# Led.net
KiCad netlist of a schematic drawn in Altium Designer
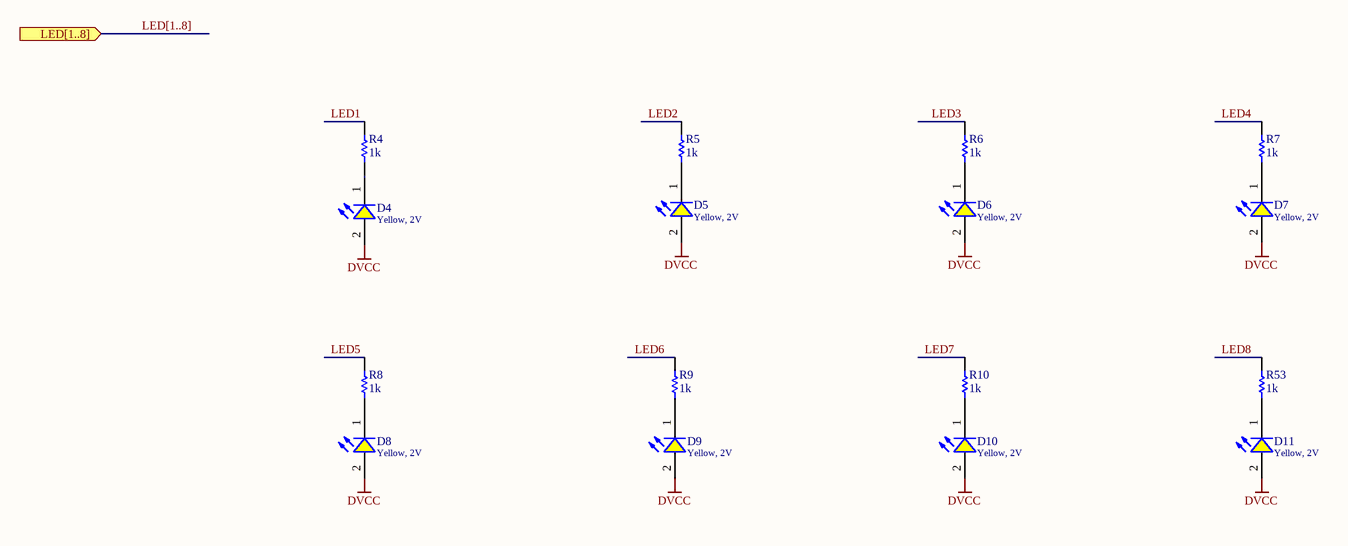
[diagram p0: Led.SchDoc]

(export (version "E")
  (design (tool "Eeschema 10.0.6"))
  (components
    (comp (ref "D4")
      (value "Yellow, 2V")
      (footprint "WL-SMCW_0603_H=0.7mm")
      (description "WL-SMCW SMT Mono-color Chip LED Waterclear, size 0603, Yellow, 2V, 140deg")
      (fields (field (name "MPN") "150060YS75000") (field (name "MF") "Wurth Elektronik"))
      (libsource (lib "Componentes_SOC") (part "150060YS75000"))
    )
    (comp (ref "D5")
      (value "Yellow, 2V")
      (footprint "WL-SMCW_0603_H=0.7mm")
      (description "WL-SMCW SMT Mono-color Chip LED Waterclear, size 0603, Yellow, 2V, 140deg")
      (fields (field (name "MPN") "150060YS75000") (field (name "MF") "Wurth Elektronik"))
      (libsource (lib "Componentes_SOC") (part "150060YS75000"))
    )
    (comp (ref "D6")
      (value "Yellow, 2V")
      (footprint "WL-SMCW_0603_H=0.7mm")
      (description "WL-SMCW SMT Mono-color Chip LED Waterclear, size 0603, Yellow, 2V, 140deg")
      (fields (field (name "MPN") "150060YS75000") (field (name "MF") "Wurth Elektronik"))
      (libsource (lib "Componentes_SOC") (part "150060YS75000"))
    )
    (comp (ref "D7")
      (value "Yellow, 2V")
      (footprint "WL-SMCW_0603_H=0.7mm")
      (description "WL-SMCW SMT Mono-color Chip LED Waterclear, size 0603, Yellow, 2V, 140deg")
      (fields (field (name "MPN") "150060YS75000") (field (name "MF") "Wurth Elektronik"))
      (libsource (lib "Componentes_SOC") (part "150060YS75000"))
    )
    (comp (ref "D8")
      (value "Yellow, 2V")
      (footprint "WL-SMCW_0603_H=0.7mm")
      (description "WL-SMCW SMT Mono-color Chip LED Waterclear, size 0603, Yellow, 2V, 140deg")
      (fields (field (name "MPN") "150060YS75000") (field (name "MF") "Wurth Elektronik"))
      (libsource (lib "Componentes_SOC") (part "150060YS75000"))
    )
    (comp (ref "D9")
      (value "Yellow, 2V")
      (footprint "WL-SMCW_0603_H=0.7mm")
      (description "WL-SMCW SMT Mono-color Chip LED Waterclear, size 0603, Yellow, 2V, 140deg")
      (fields (field (name "MPN") "150060YS75000") (field (name "MF") "Wurth Elektronik"))
      (libsource (lib "Componentes_SOC") (part "150060YS75000"))
    )
    (comp (ref "D10")
      (value "Yellow, 2V")
      (footprint "WL-SMCW_0603_H=0.7mm")
      (description "WL-SMCW SMT Mono-color Chip LED Waterclear, size 0603, Yellow, 2V, 140deg")
      (fields (field (name "MPN") "150060YS75000") (field (name "MF") "Wurth Elektronik"))
      (libsource (lib "Componentes_SOC") (part "150060YS75000"))
    )
    (comp (ref "D11")
      (value "Yellow, 2V")
      (footprint "WL-SMCW_0603_H=0.7mm")
      (description "WL-SMCW SMT Mono-color Chip LED Waterclear, size 0603, Yellow, 2V, 140deg")
      (fields (field (name "MPN") "150060YS75000") (field (name "MF") "Wurth Elektronik"))
      (libsource (lib "Componentes_SOC") (part "150060YS75000"))
    )
    (comp (ref "R4")
      (value "1k")
      (footprint "RES_0603")
      (fields
        (field (name "MPN") "RC0603FR-071KL")
        (field (name "TOLERANCE") "1%")
        (field (name "PUBLISHER") "Altium Limited")
      )
      (libsource (lib "Componentes_SOC") (part "Res0603"))
    )
    (comp (ref "R5")
      (value "1k")
      (footprint "RES_0603")
      (fields
        (field (name "MPN") "RC0603FR-071KL")
        (field (name "TOLERANCE") "1%")
        (field (name "PUBLISHER") "Altium Limited")
      )
      (libsource (lib "Componentes_SOC") (part "Res0603"))
    )
    (comp (ref "R6")
      (value "1k")
      (footprint "RES_0603")
      (fields
        (field (name "MPN") "RC0603FR-071KL")
        (field (name "TOLERANCE") "1%")
        (field (name "PUBLISHER") "Altium Limited")
      )
      (libsource (lib "Componentes_SOC") (part "Res0603"))
    )
    (comp (ref "R7")
      (value "1k")
      (footprint "RES_0603")
      (fields
        (field (name "MPN") "RC0603FR-071KL")
        (field (name "TOLERANCE") "1%")
        (field (name "PUBLISHER") "Altium Limited")
      )
      (libsource (lib "Componentes_SOC") (part "Res0603"))
    )
    (comp (ref "R8")
      (value "1k")
      (footprint "RES_0603")
      (fields
        (field (name "MPN") "RC0603FR-071KL")
        (field (name "TOLERANCE") "1%")
        (field (name "PUBLISHER") "Altium Limited")
      )
      (libsource (lib "Componentes_SOC") (part "Res0603"))
    )
    (comp (ref "R9")
      (value "1k")
      (footprint "RES_0603")
      (fields
        (field (name "MPN") "RC0603FR-071KL")
        (field (name "TOLERANCE") "1%")
        (field (name "PUBLISHER") "Altium Limited")
      )
      (libsource (lib "Componentes_SOC") (part "Res0603"))
    )
    (comp (ref "R10")
      (value "1k")
      (footprint "RES_0603")
      (fields
        (field (name "MPN") "RC0603FR-071KL")
        (field (name "TOLERANCE") "1%")
        (field (name "PUBLISHER") "Altium Limited")
      )
      (libsource (lib "Componentes_SOC") (part "Res0603"))
    )
    (comp (ref "R53")
      (value "1k")
      (footprint "RES_0603")
      (fields
        (field (name "MPN") "RC0603FR-071KL")
        (field (name "TOLERANCE") "1%")
        (field (name "PUBLISHER") "Altium Limited")
      )
      (libsource (lib "Componentes_SOC") (part "Res0603"))
    )
  )
  (nets
    (net (code "1") (name "/LED1") (class "Default")
      (node (ref "R4") (pin "2") (pinfunction "2_2") (pintype "passive"))
    )
    (net (code "2") (name "/LED2") (class "Default")
      (node (ref "R5") (pin "2") (pinfunction "2_2") (pintype "passive"))
    )
    (net (code "3") (name "/LED3") (class "Default")
      (node (ref "R6") (pin "2") (pinfunction "2_2") (pintype "passive"))
    )
    (net (code "4") (name "/LED4") (class "Default")
      (node (ref "R7") (pin "2") (pinfunction "2_2") (pintype "passive"))
    )
    (net (code "5") (name "/LED5") (class "Default")
      (node (ref "R8") (pin "2") (pinfunction "2_2") (pintype "passive"))
    )
    (net (code "6") (name "/LED6") (class "Default")
      (node (ref "R9") (pin "2") (pinfunction "2_2") (pintype "passive"))
    )
    (net (code "7") (name "/LED7") (class "Default")
      (node (ref "R10") (pin "2") (pinfunction "2_2") (pintype "passive"))
    )
    (net (code "8") (name "/LED8") (class "Default")
      (node (ref "R53") (pin "2") (pinfunction "2_2") (pintype "passive"))
    )
    (net (code "10") (name "DVCC") (class "Default")
      (node (ref "D10") (pin "2") (pinfunction "A_2") (pintype "passive"))
      (node (ref "D11") (pin "2") (pinfunction "A_2") (pintype "passive"))
      (node (ref "D4") (pin "2") (pinfunction "A_2") (pintype "passive"))
      (node (ref "D5") (pin "2") (pinfunction "A_2") (pintype "passive"))
      (node (ref "D6") (pin "2") (pinfunction "A_2") (pintype "passive"))
      (node (ref "D7") (pin "2") (pinfunction "A_2") (pintype "passive"))
      (node (ref "D8") (pin "2") (pinfunction "A_2") (pintype "passive"))
      (node (ref "D9") (pin "2") (pinfunction "A_2") (pintype "passive"))
    )
    (net (code "11") (name "Net-(D4-K)") (class "Default")
      (node (ref "D4") (pin "1") (pinfunction "K_1") (pintype "passive"))
      (node (ref "R4") (pin "1") (pinfunction "1_1") (pintype "passive"))
    )
    (net (code "12") (name "Net-(D5-K)") (class "Default")
      (node (ref "D5") (pin "1") (pinfunction "K_1") (pintype "passive"))
      (node (ref "R5") (pin "1") (pinfunction "1_1") (pintype "passive"))
    )
    (net (code "13") (name "Net-(D6-K)") (class "Default")
      (node (ref "D6") (pin "1") (pinfunction "K_1") (pintype "passive"))
      (node (ref "R6") (pin "1") (pinfunction "1_1") (pintype "passive"))
    )
    (net (code "14") (name "Net-(D7-K)") (class "Default")
      (node (ref "D7") (pin "1") (pinfunction "K_1") (pintype "passive"))
      (node (ref "R7") (pin "1") (pinfunction "1_1") (pintype "passive"))
    )
    (net (code "15") (name "Net-(D8-K)") (class "Default")
      (node (ref "D8") (pin "1") (pinfunction "K_1") (pintype "passive"))
      (node (ref "R8") (pin "1") (pinfunction "1_1") (pintype "passive"))
    )
    (net (code "16") (name "Net-(D9-K)") (class "Default")
      (node (ref "D9") (pin "1") (pinfunction "K_1") (pintype "passive"))
      (node (ref "R9") (pin "1") (pinfunction "1_1") (pintype "passive"))
    )
    (net (code "17") (name "Net-(D10-K)") (class "Default")
      (node (ref "D10") (pin "1") (pinfunction "K_1") (pintype "passive"))
      (node (ref "R10") (pin "1") (pinfunction "1_1") (pintype "passive"))
    )
    (net (code "18") (name "Net-(D11-K)") (class "Default")
      (node (ref "D11") (pin "1") (pinfunction "K_1") (pintype "passive"))
      (node (ref "R53") (pin "1") (pinfunction "1_1") (pintype "passive"))
    )
  )
)
